# VREF_DAC.net
KiCad netlist of a schematic drawn in Altium Designer
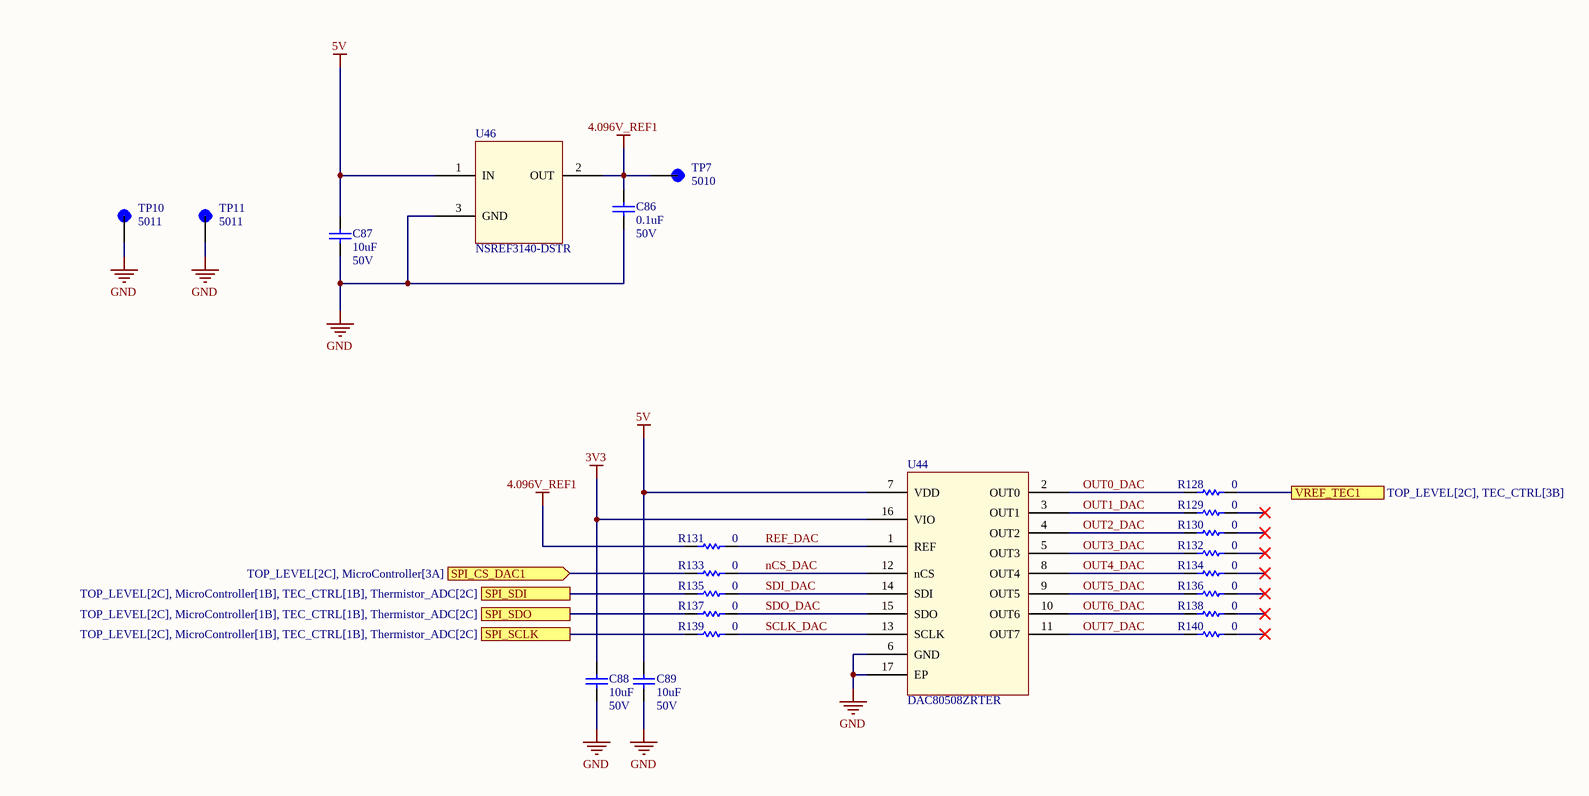
[diagram p0: VREF_DAC.SchDoc]

(export (version "E")
  (design (tool "Eeschema 10.0.6"))
  (components
    (comp (ref "C86")
      (value "0.1uF")
      (footprint "DEFAULT_CAPACITOR_0805")
      (description "CAP CER 0.1UF 50V X7R 0805")
      (fields
        (field (name "MANUFACTURER") "Cal-Chip Electronics, Inc.")
        (field (name "RATING") "50V")
        (field (name "Comment") "KGM21NR71H104KT")
      )
      (libsource (lib "Avery Altium Llibrary") (part "KGM21NR71H104KT"))
    )
    (comp (ref "C87")
      (value "10uF")
      (footprint "DEFAULT_CAPACITOR_0805")
      (description "CAP CER 10UF 50V X5R 0805")
      (fields (field (name "RATING") "50V") (field (name "Comment") "GRM21BR61H106KE43L"))
      (libsource (lib "Avery Altium Llibrary") (part "GRM21BR61H106KE43L"))
    )
    (comp (ref "C88")
      (value "10uF")
      (footprint "DEFAULT_CAPACITOR_0805")
      (description "CAP CER 10UF 50V X5R 0805")
      (fields (field (name "RATING") "50V") (field (name "Comment") "GRM21BR61H106KE43L"))
      (libsource (lib "Avery Altium Llibrary") (part "GRM21BR61H106KE43L"))
    )
    (comp (ref "C89")
      (value "10uF")
      (footprint "DEFAULT_CAPACITOR_0805")
      (description "CAP CER 10UF 50V X5R 0805")
      (fields (field (name "RATING") "50V") (field (name "Comment") "GRM21BR61H106KE43L"))
      (libsource (lib "Avery Altium Llibrary") (part "GRM21BR61H106KE43L"))
    )
    (comp (ref "R128")
      (value "0")
      (footprint "DEFAULT_RESISTOR_0805")
      (description "RES 0 OHM JUMPER 1/8W 0805")
      (fields (field (name "POWER") "1/8W") (field (name "Comment") "RC0805JR-070RL"))
      (libsource (lib "Avery Altium Llibrary") (part "RC0805JR-070RL"))
    )
    (comp (ref "R129")
      (value "0")
      (footprint "DEFAULT_RESISTOR_0805")
      (description "RES 0 OHM JUMPER 1/8W 0805")
      (fields (field (name "POWER") "1/8W") (field (name "Comment") "RC0805JR-070RL"))
      (libsource (lib "Avery Altium Llibrary") (part "RC0805JR-070RL"))
    )
    (comp (ref "R130")
      (value "0")
      (footprint "DEFAULT_RESISTOR_0805")
      (description "RES 0 OHM JUMPER 1/8W 0805")
      (fields (field (name "POWER") "1/8W") (field (name "Comment") "RC0805JR-070RL"))
      (libsource (lib "Avery Altium Llibrary") (part "RC0805JR-070RL"))
    )
    (comp (ref "R131")
      (value "0")
      (footprint "DEFAULT_RESISTOR_0805")
      (description "RES 0 OHM JUMPER 1/8W 0805")
      (fields (field (name "POWER") "1/8W") (field (name "Comment") "RC0805JR-070RL"))
      (libsource (lib "Avery Altium Llibrary") (part "RC0805JR-070RL"))
    )
    (comp (ref "R132")
      (value "0")
      (footprint "DEFAULT_RESISTOR_0805")
      (description "RES 0 OHM JUMPER 1/8W 0805")
      (fields (field (name "POWER") "1/8W") (field (name "Comment") "RC0805JR-070RL"))
      (libsource (lib "Avery Altium Llibrary") (part "RC0805JR-070RL"))
    )
    (comp (ref "R133")
      (value "0")
      (footprint "DEFAULT_RESISTOR_0805")
      (description "RES 0 OHM JUMPER 1/8W 0805")
      (fields (field (name "POWER") "1/8W") (field (name "Comment") "RC0805JR-070RL"))
      (libsource (lib "Avery Altium Llibrary") (part "RC0805JR-070RL"))
    )
    (comp (ref "R134")
      (value "0")
      (footprint "DEFAULT_RESISTOR_0805")
      (description "RES 0 OHM JUMPER 1/8W 0805")
      (fields (field (name "POWER") "1/8W") (field (name "Comment") "RC0805JR-070RL"))
      (libsource (lib "Avery Altium Llibrary") (part "RC0805JR-070RL"))
    )
    (comp (ref "R135")
      (value "0")
      (footprint "DEFAULT_RESISTOR_0805")
      (description "RES 0 OHM JUMPER 1/8W 0805")
      (fields (field (name "POWER") "1/8W") (field (name "Comment") "RC0805JR-070RL"))
      (libsource (lib "Avery Altium Llibrary") (part "RC0805JR-070RL"))
    )
    (comp (ref "R136")
      (value "0")
      (footprint "DEFAULT_RESISTOR_0805")
      (description "RES 0 OHM JUMPER 1/8W 0805")
      (fields (field (name "POWER") "1/8W") (field (name "Comment") "RC0805JR-070RL"))
      (libsource (lib "Avery Altium Llibrary") (part "RC0805JR-070RL"))
    )
    (comp (ref "R137")
      (value "0")
      (footprint "DEFAULT_RESISTOR_0805")
      (description "RES 0 OHM JUMPER 1/8W 0805")
      (fields (field (name "POWER") "1/8W") (field (name "Comment") "RC0805JR-070RL"))
      (libsource (lib "Avery Altium Llibrary") (part "RC0805JR-070RL"))
    )
    (comp (ref "R138")
      (value "0")
      (footprint "DEFAULT_RESISTOR_0805")
      (description "RES 0 OHM JUMPER 1/8W 0805")
      (fields (field (name "POWER") "1/8W") (field (name "Comment") "RC0805JR-070RL"))
      (libsource (lib "Avery Altium Llibrary") (part "RC0805JR-070RL"))
    )
    (comp (ref "R139")
      (value "0")
      (footprint "DEFAULT_RESISTOR_0805")
      (description "RES 0 OHM JUMPER 1/8W 0805")
      (fields (field (name "POWER") "1/8W") (field (name "Comment") "RC0805JR-070RL"))
      (libsource (lib "Avery Altium Llibrary") (part "RC0805JR-070RL"))
    )
    (comp (ref "R140")
      (value "0")
      (footprint "DEFAULT_RESISTOR_0805")
      (description "RES 0 OHM JUMPER 1/8W 0805")
      (fields (field (name "POWER") "1/8W") (field (name "Comment") "RC0805JR-070RL"))
      (libsource (lib "Avery Altium Llibrary") (part "RC0805JR-070RL"))
    )
    (comp (ref "TP7")
      (value "5010")
      (footprint "TP_5011")
      (description "PC TEST POINT MULTIPURPOSE RED")
      (libsource (lib "Avery Altium Llibrary") (part "5010"))
    )
    (comp (ref "TP10")
      (value "5011")
      (footprint "TP_5011")
      (description "PC TEST POINT MULTIPURPOSE BLACK")
      (fields (field (name "MF") "Keystone Electronics Corp."))
      (libsource (lib "Avery Altium Llibrary") (part "5011"))
    )
    (comp (ref "TP11")
      (value "5011")
      (footprint "TP_5011")
      (description "PC TEST POINT MULTIPURPOSE BLACK")
      (fields (field (name "MF") "Keystone Electronics Corp."))
      (libsource (lib "Avery Altium Llibrary") (part "5011"))
    )
    (comp (ref "U44")
      (value "DAC80508ZRTER")
      (footprint "DAC80508ZRTER-WQFN16")
      (description "IC DAC 16BIT V-OUT 16WQFN")
      (fields (field (name "MANUFACTURER") "Texas Instruments"))
      (libsource (lib "Avery Altium Llibrary") (part "DAC80508ZRTER"))
    )
    (comp (ref "U46")
      (value "NSREF3140-DSTR")
      (footprint "NSREF3140DSTR-SOT23-3L")
      (description "0.2% ACCURACY 15PPM 4V REF")
      (fields (field (name "MANUFACTURER") "NOVOSENSE"))
      (libsource (lib "Avery Altium Llibrary") (part "NSREF3140-DSTR"))
    )
  )
  (nets
    (net (code "1") (name "/OUT0_DAC") (class "Default")
      (node (ref "R128") (pin "2") (pinfunction "2_2") (pintype "passive"))
      (node (ref "U44") (pin "2") (pinfunction "OUT0_2") (pintype "passive"))
    )
    (net (code "2") (name "/OUT1_DAC") (class "Default")
      (node (ref "R129") (pin "2") (pinfunction "2_2") (pintype "passive"))
      (node (ref "U44") (pin "3") (pinfunction "OUT1_3") (pintype "passive"))
    )
    (net (code "3") (name "/OUT2_DAC") (class "Default")
      (node (ref "R130") (pin "2") (pinfunction "2_2") (pintype "passive"))
      (node (ref "U44") (pin "4") (pinfunction "OUT2_4") (pintype "passive"))
    )
    (net (code "4") (name "/OUT3_DAC") (class "Default")
      (node (ref "R132") (pin "2") (pinfunction "2_2") (pintype "passive"))
      (node (ref "U44") (pin "5") (pinfunction "OUT3_5") (pintype "passive"))
    )
    (net (code "5") (name "/OUT4_DAC") (class "Default")
      (node (ref "R134") (pin "2") (pinfunction "2_2") (pintype "passive"))
      (node (ref "U44") (pin "8") (pinfunction "OUT4_8") (pintype "passive"))
    )
    (net (code "6") (name "/OUT5_DAC") (class "Default")
      (node (ref "R136") (pin "2") (pinfunction "2_2") (pintype "passive"))
      (node (ref "U44") (pin "9") (pinfunction "OUT5_9") (pintype "passive"))
    )
    (net (code "7") (name "/OUT6_DAC") (class "Default")
      (node (ref "R138") (pin "2") (pinfunction "2_2") (pintype "passive"))
      (node (ref "U44") (pin "10") (pinfunction "OUT6_10") (pintype "passive"))
    )
    (net (code "8") (name "/OUT7_DAC") (class "Default")
      (node (ref "R140") (pin "2") (pinfunction "2_2") (pintype "passive"))
      (node (ref "U44") (pin "11") (pinfunction "OUT7_11") (pintype "passive"))
    )
    (net (code "9") (name "/REF_DAC") (class "Default")
      (node (ref "R131") (pin "1") (pinfunction "1_1") (pintype "passive"))
      (node (ref "U44") (pin "1") (pinfunction "REF_1") (pintype "passive"))
    )
    (net (code "10") (name "/SCLK_DAC") (class "Default")
      (node (ref "R139") (pin "1") (pinfunction "1_1") (pintype "passive"))
      (node (ref "U44") (pin "13") (pinfunction "SCLK_13") (pintype "passive"))
    )
    (net (code "11") (name "/SDI_DAC") (class "Default")
      (node (ref "R135") (pin "1") (pinfunction "1_1") (pintype "passive"))
      (node (ref "U44") (pin "14") (pinfunction "SDI_14") (pintype "passive"))
    )
    (net (code "12") (name "/SDO_DAC") (class "Default")
      (node (ref "R137") (pin "1") (pinfunction "1_1") (pintype "passive"))
      (node (ref "U44") (pin "15") (pinfunction "SDO_15") (pintype "passive"))
    )
    (net (code "13") (name "/SPI_CS_DAC1") (class "Default")
      (node (ref "R133") (pin "2") (pinfunction "2_2") (pintype "passive"))
    )
    (net (code "14") (name "/SPI_SCLK") (class "Default")
      (node (ref "R139") (pin "2") (pinfunction "2_2") (pintype "passive"))
    )
    (net (code "15") (name "/SPI_SDI") (class "Default")
      (node (ref "R135") (pin "2") (pinfunction "2_2") (pintype "passive"))
    )
    (net (code "16") (name "/SPI_SDO") (class "Default")
      (node (ref "R137") (pin "2") (pinfunction "2_2") (pintype "passive"))
    )
    (net (code "17") (name "/VREF_TEC1") (class "Default")
      (node (ref "R128") (pin "1") (pinfunction "1_1") (pintype "passive"))
    )
    (net (code "18") (name "/nCS_DAC") (class "Default")
      (node (ref "R133") (pin "1") (pinfunction "1_1") (pintype "passive"))
      (node (ref "U44") (pin "12") (pinfunction "nCS_12") (pintype "passive"))
    )
    (net (code "19") (name "3V3") (class "Default")
      (node (ref "C88") (pin "2") (pinfunction "2_2") (pintype "passive"))
      (node (ref "U44") (pin "16") (pinfunction "VIO_16") (pintype "passive"))
    )
    (net (code "20") (name "4.096V_REF1") (class "Default")
      (node (ref "C86") (pin "2") (pinfunction "2_2") (pintype "passive"))
      (node (ref "R131") (pin "2") (pinfunction "2_2") (pintype "passive"))
      (node (ref "TP7") (pin "TP") (pinfunction "TP_TP") (pintype "passive"))
      (node (ref "U46") (pin "2") (pinfunction "OUT_2") (pintype "passive"))
    )
    (net (code "21") (name "5V") (class "Default")
      (node (ref "C87") (pin "2") (pinfunction "2_2") (pintype "passive"))
      (node (ref "C89") (pin "2") (pinfunction "2_2") (pintype "passive"))
      (node (ref "U44") (pin "7") (pinfunction "VDD_7") (pintype "passive"))
      (node (ref "U46") (pin "1") (pinfunction "IN_1") (pintype "passive"))
    )
    (net (code "22") (name "GND") (class "Default")
      (node (ref "C86") (pin "1") (pinfunction "1_1") (pintype "passive"))
      (node (ref "C87") (pin "1") (pinfunction "1_1") (pintype "passive"))
      (node (ref "C88") (pin "1") (pinfunction "1_1") (pintype "passive"))
      (node (ref "C89") (pin "1") (pinfunction "1_1") (pintype "passive"))
      (node (ref "TP10") (pin "TP") (pinfunction "TP_TP") (pintype "passive"))
      (node (ref "TP11") (pin "TP") (pinfunction "TP_TP") (pintype "passive"))
      (node (ref "U44") (pin "17") (pinfunction "EP_17") (pintype "passive"))
      (node (ref "U44") (pin "6") (pinfunction "GND_6") (pintype "passive"))
      (node (ref "U46") (pin "3") (pinfunction "GND_3") (pintype "passive"))
    )
    (net (code "23") (name "unconnected-(R129-Pad1)") (class "Default")
      (node (ref "R129") (pin "1") (pinfunction "1_1") (pintype "passive+no_connect"))
    )
    (net (code "24") (name "unconnected-(R130-Pad1)") (class "Default")
      (node (ref "R130") (pin "1") (pinfunction "1_1") (pintype "passive+no_connect"))
    )
    (net (code "25") (name "unconnected-(R132-Pad1)") (class "Default")
      (node (ref "R132") (pin "1") (pinfunction "1_1") (pintype "passive+no_connect"))
    )
    (net (code "26") (name "unconnected-(R134-Pad1)") (class "Default")
      (node (ref "R134") (pin "1") (pinfunction "1_1") (pintype "passive+no_connect"))
    )
    (net (code "27") (name "unconnected-(R136-Pad1)") (class "Default")
      (node (ref "R136") (pin "1") (pinfunction "1_1") (pintype "passive+no_connect"))
    )
    (net (code "28") (name "unconnected-(R138-Pad1)") (class "Default")
      (node (ref "R138") (pin "1") (pinfunction "1_1") (pintype "passive+no_connect"))
    )
    (net (code "29") (name "unconnected-(R140-Pad1)") (class "Default")
      (node (ref "R140") (pin "1") (pinfunction "1_1") (pintype "passive+no_connect"))
    )
  )
)
